# SpotiFi.net
KiCad netlist of a schematic drawn in EasyEDA
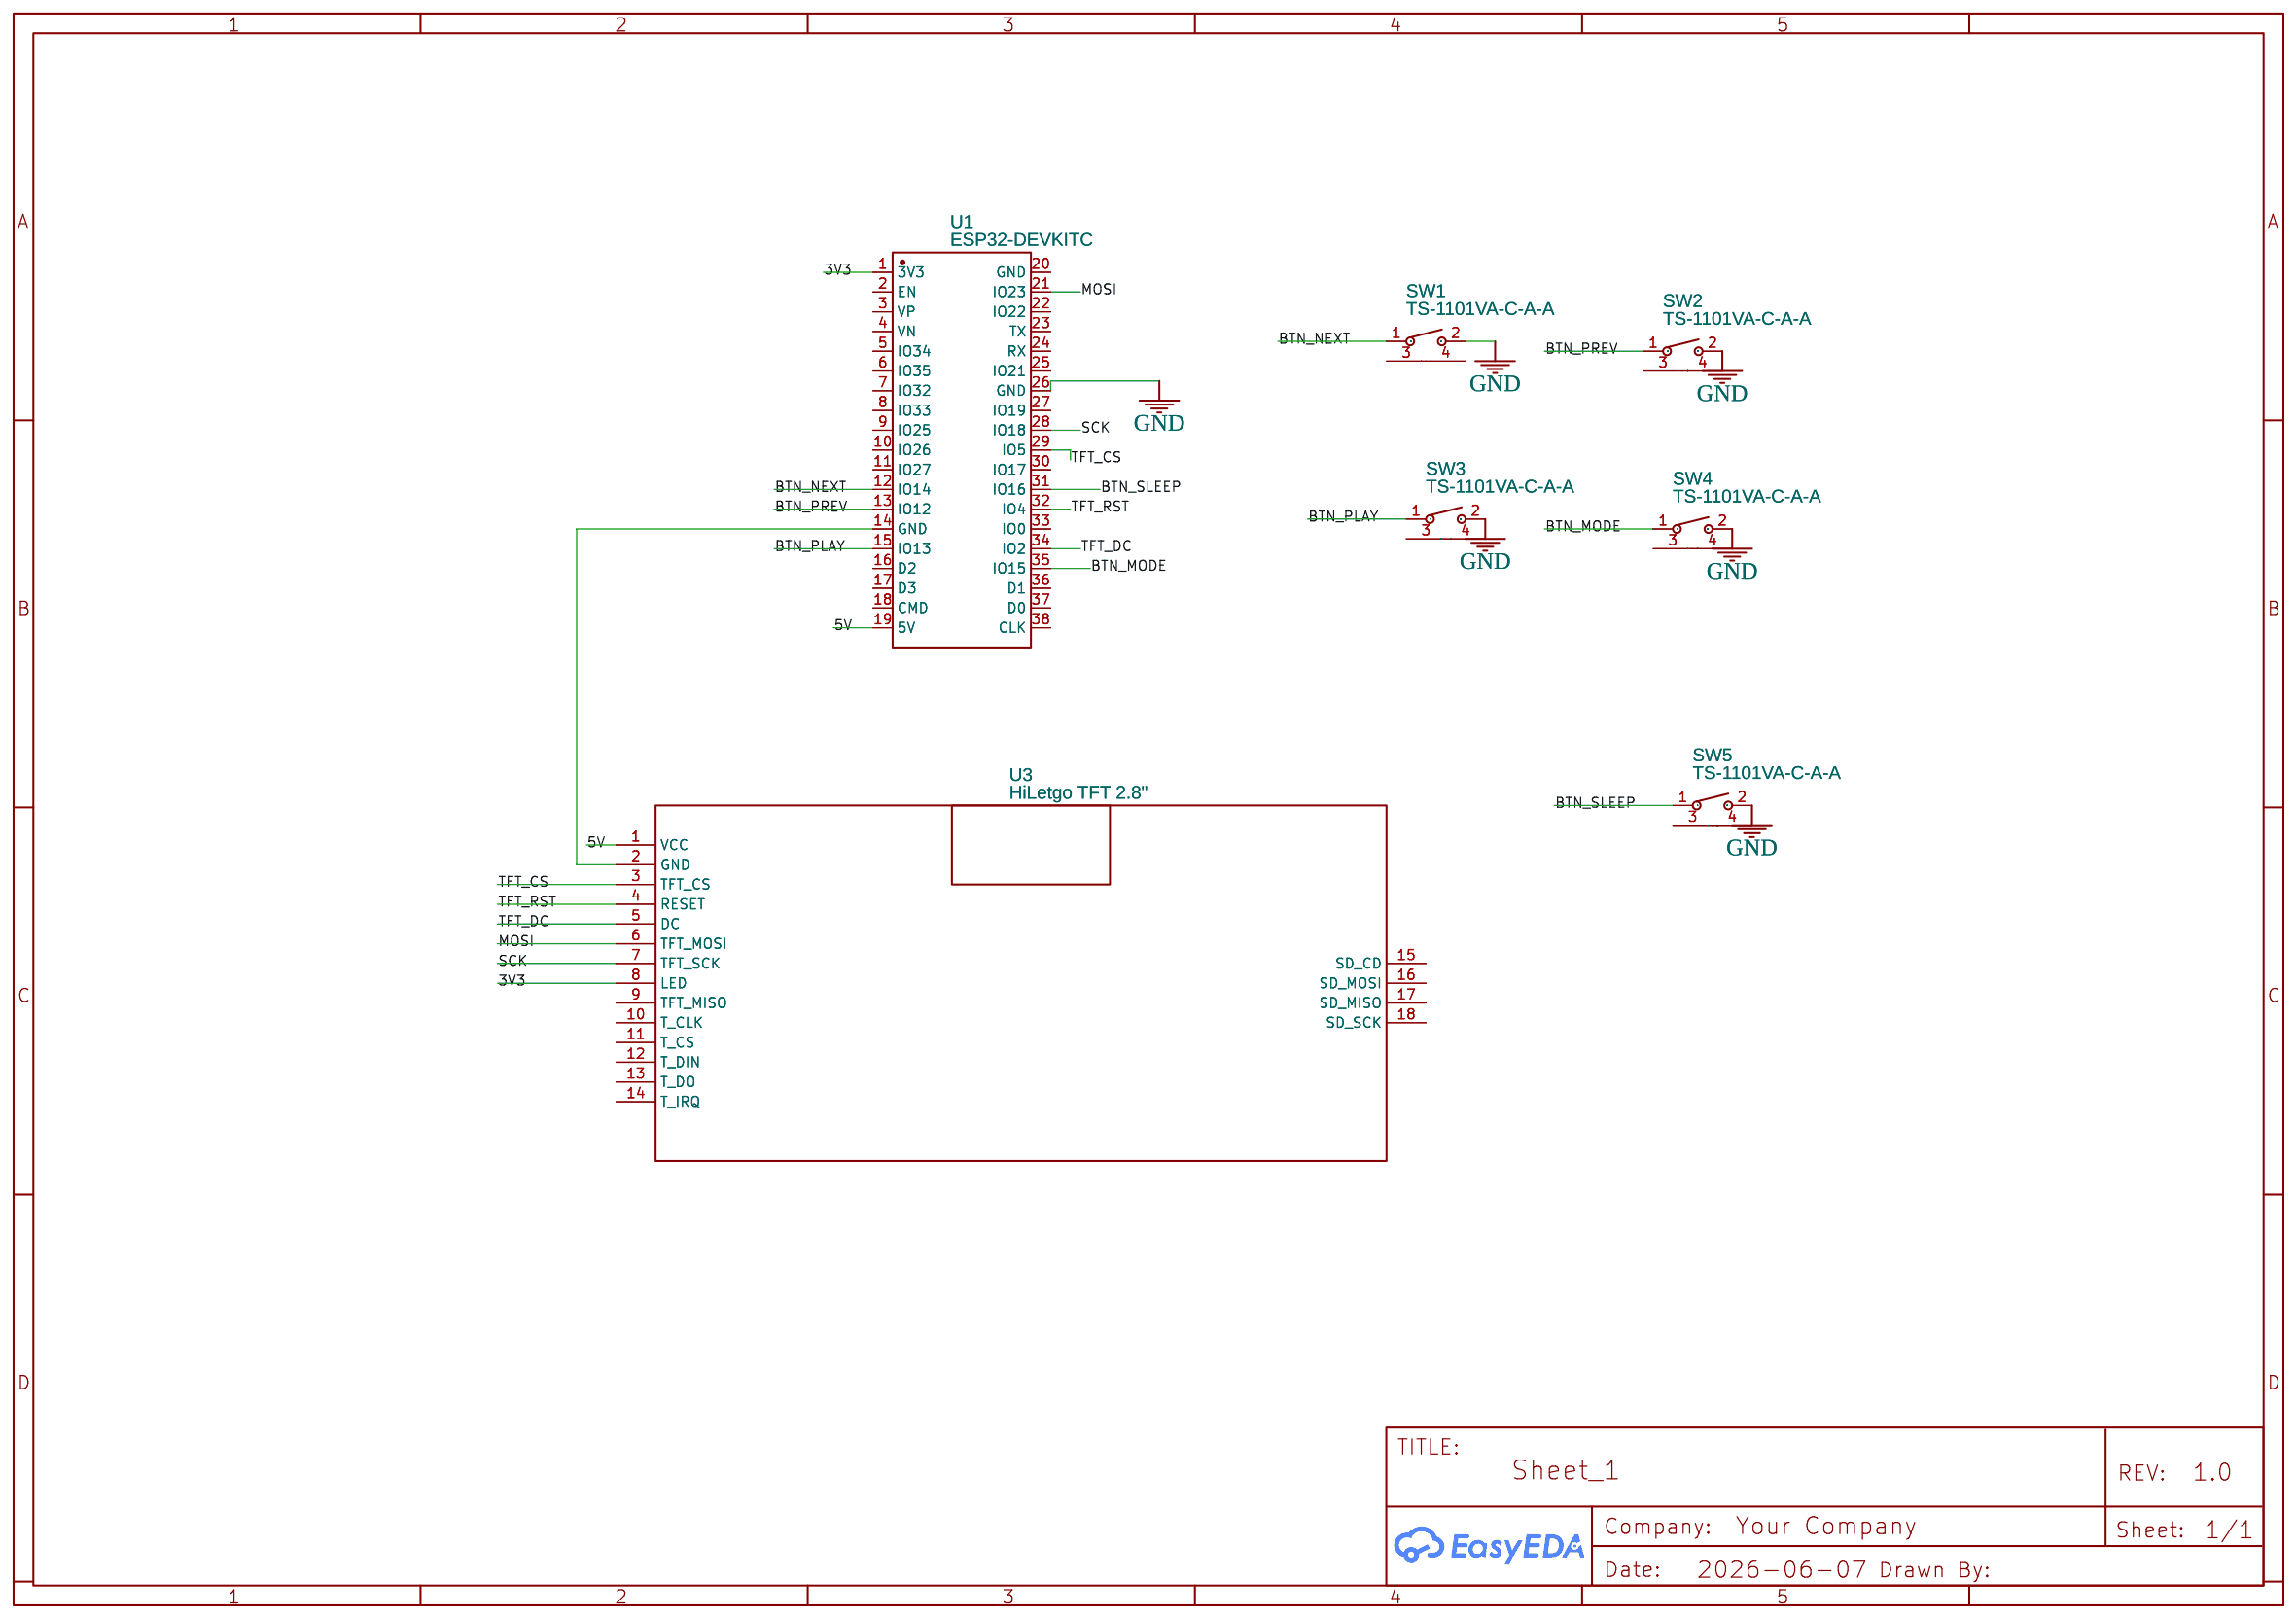
[diagram p0: schematic sheet]

(export (version "E")
  (design (tool "Eeschema 10.0.6"))
  (components
    (comp (ref "SW1")
      (value "TS-1101VA-C-A-A")
      (fields (field (name "Manufacturer") "XKB Connection(中国星坤)"))
      (libsource (lib "") (part "TS-1101VA-C-A-A"))
    )
    (comp (ref "SW2")
      (value "TS-1101VA-C-A-A")
      (fields (field (name "Manufacturer") "XKB Connection(中国星坤)"))
      (libsource (lib "") (part "TS-1101VA-C-A-A"))
    )
    (comp (ref "SW3")
      (value "TS-1101VA-C-A-A")
      (fields (field (name "Manufacturer") "XKB Connection(中国星坤)"))
      (libsource (lib "") (part "TS-1101VA-C-A-A"))
    )
    (comp (ref "SW4")
      (value "TS-1101VA-C-A-A")
      (fields (field (name "Manufacturer") "XKB Connection(中国星坤)"))
      (libsource (lib "") (part "TS-1101VA-C-A-A"))
    )
    (comp (ref "SW5")
      (value "TS-1101VA-C-A-A")
      (fields (field (name "Manufacturer") "XKB Connection(中国星坤)"))
      (libsource (lib "") (part "TS-1101VA-C-A-A"))
    )
    (comp (ref "U1")
      (value "ESP32-DEVKITC")
      (fields
        (field (name "Manufacturer Part") "ESP32-DevKitC")
        (field (name "Manufacturer") "ESPRESSIF(乐鑫)")
      )
      (libsource (lib "") (part "ESP32-DEVKITC"))
    )
    (comp (ref "U3") (value "HiLetgo TFT 2.8\"") (libsource (lib "") (part "HiLetgo TFT 2.8{dblquote}")))
  )
  (nets
    (net (code "1") (name "/3V3") (class "Default")
      (node (ref "U1") (pin "1") (pinfunction "3V3_1") (pintype "unspecified"))
      (node (ref "U3") (pin "8") (pinfunction "LED_8") (pintype "unspecified"))
    )
    (net (code "2") (name "/5V") (class "Default")
      (node (ref "U1") (pin "19") (pinfunction "5V_19") (pintype "unspecified"))
      (node (ref "U3") (pin "1") (pinfunction "VCC_1") (pintype "unspecified"))
    )
    (net (code "3") (name "/BTN_MODE") (class "Default")
      (node (ref "SW4") (pin "1") (pinfunction "1_1") (pintype "unspecified"))
      (node (ref "U1") (pin "35") (pinfunction "IO15_35") (pintype "unspecified"))
    )
    (net (code "4") (name "/BTN_NEXT") (class "Default")
      (node (ref "SW1") (pin "1") (pinfunction "1_1") (pintype "unspecified"))
      (node (ref "U1") (pin "12") (pinfunction "IO14_12") (pintype "unspecified"))
    )
    (net (code "5") (name "/BTN_PLAY") (class "Default")
      (node (ref "SW3") (pin "1") (pinfunction "1_1") (pintype "unspecified"))
      (node (ref "U1") (pin "15") (pinfunction "IO13_15") (pintype "unspecified"))
    )
    (net (code "6") (name "/BTN_PREV") (class "Default")
      (node (ref "SW2") (pin "1") (pinfunction "1_1") (pintype "unspecified"))
      (node (ref "U1") (pin "13") (pinfunction "IO12_13") (pintype "unspecified"))
    )
    (net (code "7") (name "/BTN_SLEEP") (class "Default")
      (node (ref "SW5") (pin "1") (pinfunction "1_1") (pintype "unspecified"))
      (node (ref "U1") (pin "31") (pinfunction "IO16_31") (pintype "unspecified"))
    )
    (net (code "8") (name "/MOSI") (class "Default")
      (node (ref "U1") (pin "21") (pinfunction "IO23_21") (pintype "unspecified"))
      (node (ref "U3") (pin "6") (pinfunction "TFT_MOSI_6") (pintype "unspecified"))
    )
    (net (code "9") (name "/SCK") (class "Default")
      (node (ref "U1") (pin "28") (pinfunction "IO18_28") (pintype "unspecified"))
      (node (ref "U3") (pin "7") (pinfunction "TFT_SCK_7") (pintype "unspecified"))
    )
    (net (code "10") (name "/TFT_CS") (class "Default")
      (node (ref "U1") (pin "29") (pinfunction "IO5_29") (pintype "unspecified"))
      (node (ref "U3") (pin "3") (pinfunction "TFT_CS_3") (pintype "unspecified"))
    )
    (net (code "11") (name "/TFT_DC") (class "Default")
      (node (ref "U1") (pin "34") (pinfunction "IO2_34") (pintype "unspecified"))
      (node (ref "U3") (pin "5") (pinfunction "DC_5") (pintype "unspecified"))
    )
    (net (code "12") (name "/TFT_RST") (class "Default")
      (node (ref "U1") (pin "32") (pinfunction "IO4_32") (pintype "unspecified"))
      (node (ref "U3") (pin "4") (pinfunction "RESET_4") (pintype "unspecified"))
    )
    (net (code "13") (name "GND") (class "Default")
      (node (ref "SW1") (pin "2") (pinfunction "2_2") (pintype "unspecified"))
      (node (ref "SW2") (pin "2") (pinfunction "2_2") (pintype "unspecified"))
      (node (ref "SW3") (pin "2") (pinfunction "2_2") (pintype "unspecified"))
      (node (ref "SW4") (pin "2") (pinfunction "2_2") (pintype "unspecified"))
      (node (ref "SW5") (pin "2") (pinfunction "2_2") (pintype "unspecified"))
      (node (ref "U1") (pin "26") (pinfunction "GND_26") (pintype "unspecified"))
    )
    (net (code "14") (name "Net-(U3-GND)") (class "Default")
      (node (ref "U1") (pin "14") (pinfunction "GND_14") (pintype "unspecified"))
      (node (ref "U3") (pin "2") (pinfunction "GND_2") (pintype "unspecified"))
    )
    (net (code "15") (name "unconnected-(SW1-Pad3)") (class "Default")
      (node (ref "SW1") (pin "3") (pinfunction "3_3") (pintype "unspecified"))
    )
    (net (code "16") (name "unconnected-(SW1-Pad4)") (class "Default")
      (node (ref "SW1") (pin "4") (pinfunction "4_4") (pintype "unspecified"))
    )
    (net (code "17") (name "unconnected-(SW2-Pad3)") (class "Default")
      (node (ref "SW2") (pin "3") (pinfunction "3_3") (pintype "unspecified"))
    )
    (net (code "18") (name "unconnected-(SW2-Pad4)") (class "Default")
      (node (ref "SW2") (pin "4") (pinfunction "4_4") (pintype "unspecified"))
    )
    (net (code "19") (name "unconnected-(SW3-Pad3)") (class "Default")
      (node (ref "SW3") (pin "3") (pinfunction "3_3") (pintype "unspecified"))
    )
    (net (code "20") (name "unconnected-(SW3-Pad4)") (class "Default")
      (node (ref "SW3") (pin "4") (pinfunction "4_4") (pintype "unspecified"))
    )
    (net (code "21") (name "unconnected-(SW4-Pad3)") (class "Default")
      (node (ref "SW4") (pin "3") (pinfunction "3_3") (pintype "unspecified"))
    )
    (net (code "22") (name "unconnected-(SW4-Pad4)") (class "Default")
      (node (ref "SW4") (pin "4") (pinfunction "4_4") (pintype "unspecified"))
    )
    (net (code "23") (name "unconnected-(SW5-Pad3)") (class "Default")
      (node (ref "SW5") (pin "3") (pinfunction "3_3") (pintype "unspecified"))
    )
    (net (code "24") (name "unconnected-(SW5-Pad4)") (class "Default")
      (node (ref "SW5") (pin "4") (pinfunction "4_4") (pintype "unspecified"))
    )
    (net (code "25") (name "unconnected-(U1-CLK-Pad38)") (class "Default")
      (node (ref "U1") (pin "38") (pinfunction "CLK_38") (pintype "unspecified"))
    )
    (net (code "26") (name "unconnected-(U1-CMD-Pad18)") (class "Default")
      (node (ref "U1") (pin "18") (pinfunction "CMD_18") (pintype "unspecified"))
    )
    (net (code "27") (name "unconnected-(U1-D0-Pad37)") (class "Default")
      (node (ref "U1") (pin "37") (pinfunction "D0_37") (pintype "unspecified"))
    )
    (net (code "28") (name "unconnected-(U1-D1-Pad36)") (class "Default")
      (node (ref "U1") (pin "36") (pinfunction "D1_36") (pintype "unspecified"))
    )
    (net (code "29") (name "unconnected-(U1-D2-Pad16)") (class "Default")
      (node (ref "U1") (pin "16") (pinfunction "D2_16") (pintype "unspecified"))
    )
    (net (code "30") (name "unconnected-(U1-D3-Pad17)") (class "Default")
      (node (ref "U1") (pin "17") (pinfunction "D3_17") (pintype "unspecified"))
    )
    (net (code "31") (name "unconnected-(U1-EN-Pad2)") (class "Default")
      (node (ref "U1") (pin "2") (pinfunction "EN_2") (pintype "unspecified"))
    )
    (net (code "32") (name "unconnected-(U1-GND-Pad20)") (class "Default")
      (node (ref "U1") (pin "20") (pinfunction "GND_20") (pintype "unspecified"))
    )
    (net (code "33") (name "unconnected-(U1-IO0-Pad33)") (class "Default")
      (node (ref "U1") (pin "33") (pinfunction "IO0_33") (pintype "unspecified"))
    )
    (net (code "34") (name "unconnected-(U1-IO17-Pad30)") (class "Default")
      (node (ref "U1") (pin "30") (pinfunction "IO17_30") (pintype "unspecified"))
    )
    (net (code "35") (name "unconnected-(U1-IO19-Pad27)") (class "Default")
      (node (ref "U1") (pin "27") (pinfunction "IO19_27") (pintype "unspecified"))
    )
    (net (code "36") (name "unconnected-(U1-IO21-Pad25)") (class "Default")
      (node (ref "U1") (pin "25") (pinfunction "IO21_25") (pintype "unspecified"))
    )
    (net (code "37") (name "unconnected-(U1-IO22-Pad22)") (class "Default")
      (node (ref "U1") (pin "22") (pinfunction "IO22_22") (pintype "unspecified"))
    )
    (net (code "38") (name "unconnected-(U1-IO25-Pad9)") (class "Default")
      (node (ref "U1") (pin "9") (pinfunction "IO25_9") (pintype "unspecified"))
    )
    (net (code "39") (name "unconnected-(U1-IO26-Pad10)") (class "Default")
      (node (ref "U1") (pin "10") (pinfunction "IO26_10") (pintype "unspecified"))
    )
    (net (code "40") (name "unconnected-(U1-IO27-Pad11)") (class "Default")
      (node (ref "U1") (pin "11") (pinfunction "IO27_11") (pintype "unspecified"))
    )
    (net (code "41") (name "unconnected-(U1-IO32-Pad7)") (class "Default")
      (node (ref "U1") (pin "7") (pinfunction "IO32_7") (pintype "unspecified"))
    )
    (net (code "42") (name "unconnected-(U1-IO33-Pad8)") (class "Default")
      (node (ref "U1") (pin "8") (pinfunction "IO33_8") (pintype "unspecified"))
    )
    (net (code "43") (name "unconnected-(U1-IO34-Pad5)") (class "Default")
      (node (ref "U1") (pin "5") (pinfunction "IO34_5") (pintype "unspecified"))
    )
    (net (code "44") (name "unconnected-(U1-IO35-Pad6)") (class "Default")
      (node (ref "U1") (pin "6") (pinfunction "IO35_6") (pintype "unspecified"))
    )
    (net (code "45") (name "unconnected-(U1-RX-Pad24)") (class "Default")
      (node (ref "U1") (pin "24") (pinfunction "RX_24") (pintype "unspecified"))
    )
    (net (code "46") (name "unconnected-(U1-TX-Pad23)") (class "Default")
      (node (ref "U1") (pin "23") (pinfunction "TX_23") (pintype "unspecified"))
    )
    (net (code "47") (name "unconnected-(U1-VN-Pad4)") (class "Default")
      (node (ref "U1") (pin "4") (pinfunction "VN_4") (pintype "unspecified"))
    )
    (net (code "48") (name "unconnected-(U1-VP-Pad3)") (class "Default")
      (node (ref "U1") (pin "3") (pinfunction "VP_3") (pintype "unspecified"))
    )
    (net (code "49") (name "unconnected-(U3-SD_CD-Pad15)") (class "Default")
      (node (ref "U3") (pin "15") (pinfunction "SD_CD_15") (pintype "unspecified"))
    )
    (net (code "50") (name "unconnected-(U3-SD_MISO-Pad17)") (class "Default")
      (node (ref "U3") (pin "17") (pinfunction "SD_MISO_17") (pintype "unspecified"))
    )
    (net (code "51") (name "unconnected-(U3-SD_MOSI-Pad16)") (class "Default")
      (node (ref "U3") (pin "16") (pinfunction "SD_MOSI_16") (pintype "unspecified"))
    )
    (net (code "52") (name "unconnected-(U3-SD_SCK-Pad18)") (class "Default")
      (node (ref "U3") (pin "18") (pinfunction "SD_SCK_18") (pintype "unspecified"))
    )
    (net (code "53") (name "unconnected-(U3-TFT_MISO-Pad9)") (class "Default")
      (node (ref "U3") (pin "9") (pinfunction "TFT_MISO_9") (pintype "unspecified"))
    )
    (net (code "54") (name "unconnected-(U3-T_CLK-Pad10)") (class "Default")
      (node (ref "U3") (pin "10") (pinfunction "T_CLK_10") (pintype "unspecified"))
    )
    (net (code "55") (name "unconnected-(U3-T_CS-Pad11)") (class "Default")
      (node (ref "U3") (pin "11") (pinfunction "T_CS_11") (pintype "unspecified"))
    )
    (net (code "56") (name "unconnected-(U3-T_DIN-Pad12)") (class "Default")
      (node (ref "U3") (pin "12") (pinfunction "T_DIN_12") (pintype "unspecified"))
    )
    (net (code "57") (name "unconnected-(U3-T_DO-Pad13)") (class "Default")
      (node (ref "U3") (pin "13") (pinfunction "T_DO_13") (pintype "unspecified"))
    )
    (net (code "58") (name "unconnected-(U3-T_IRQ-Pad14)") (class "Default")
      (node (ref "U3") (pin "14") (pinfunction "T_IRQ_14") (pintype "unspecified"))
    )
  )
)
